# HVIB_v5.net
KiCad netlist of a schematic drawn in EAGLE
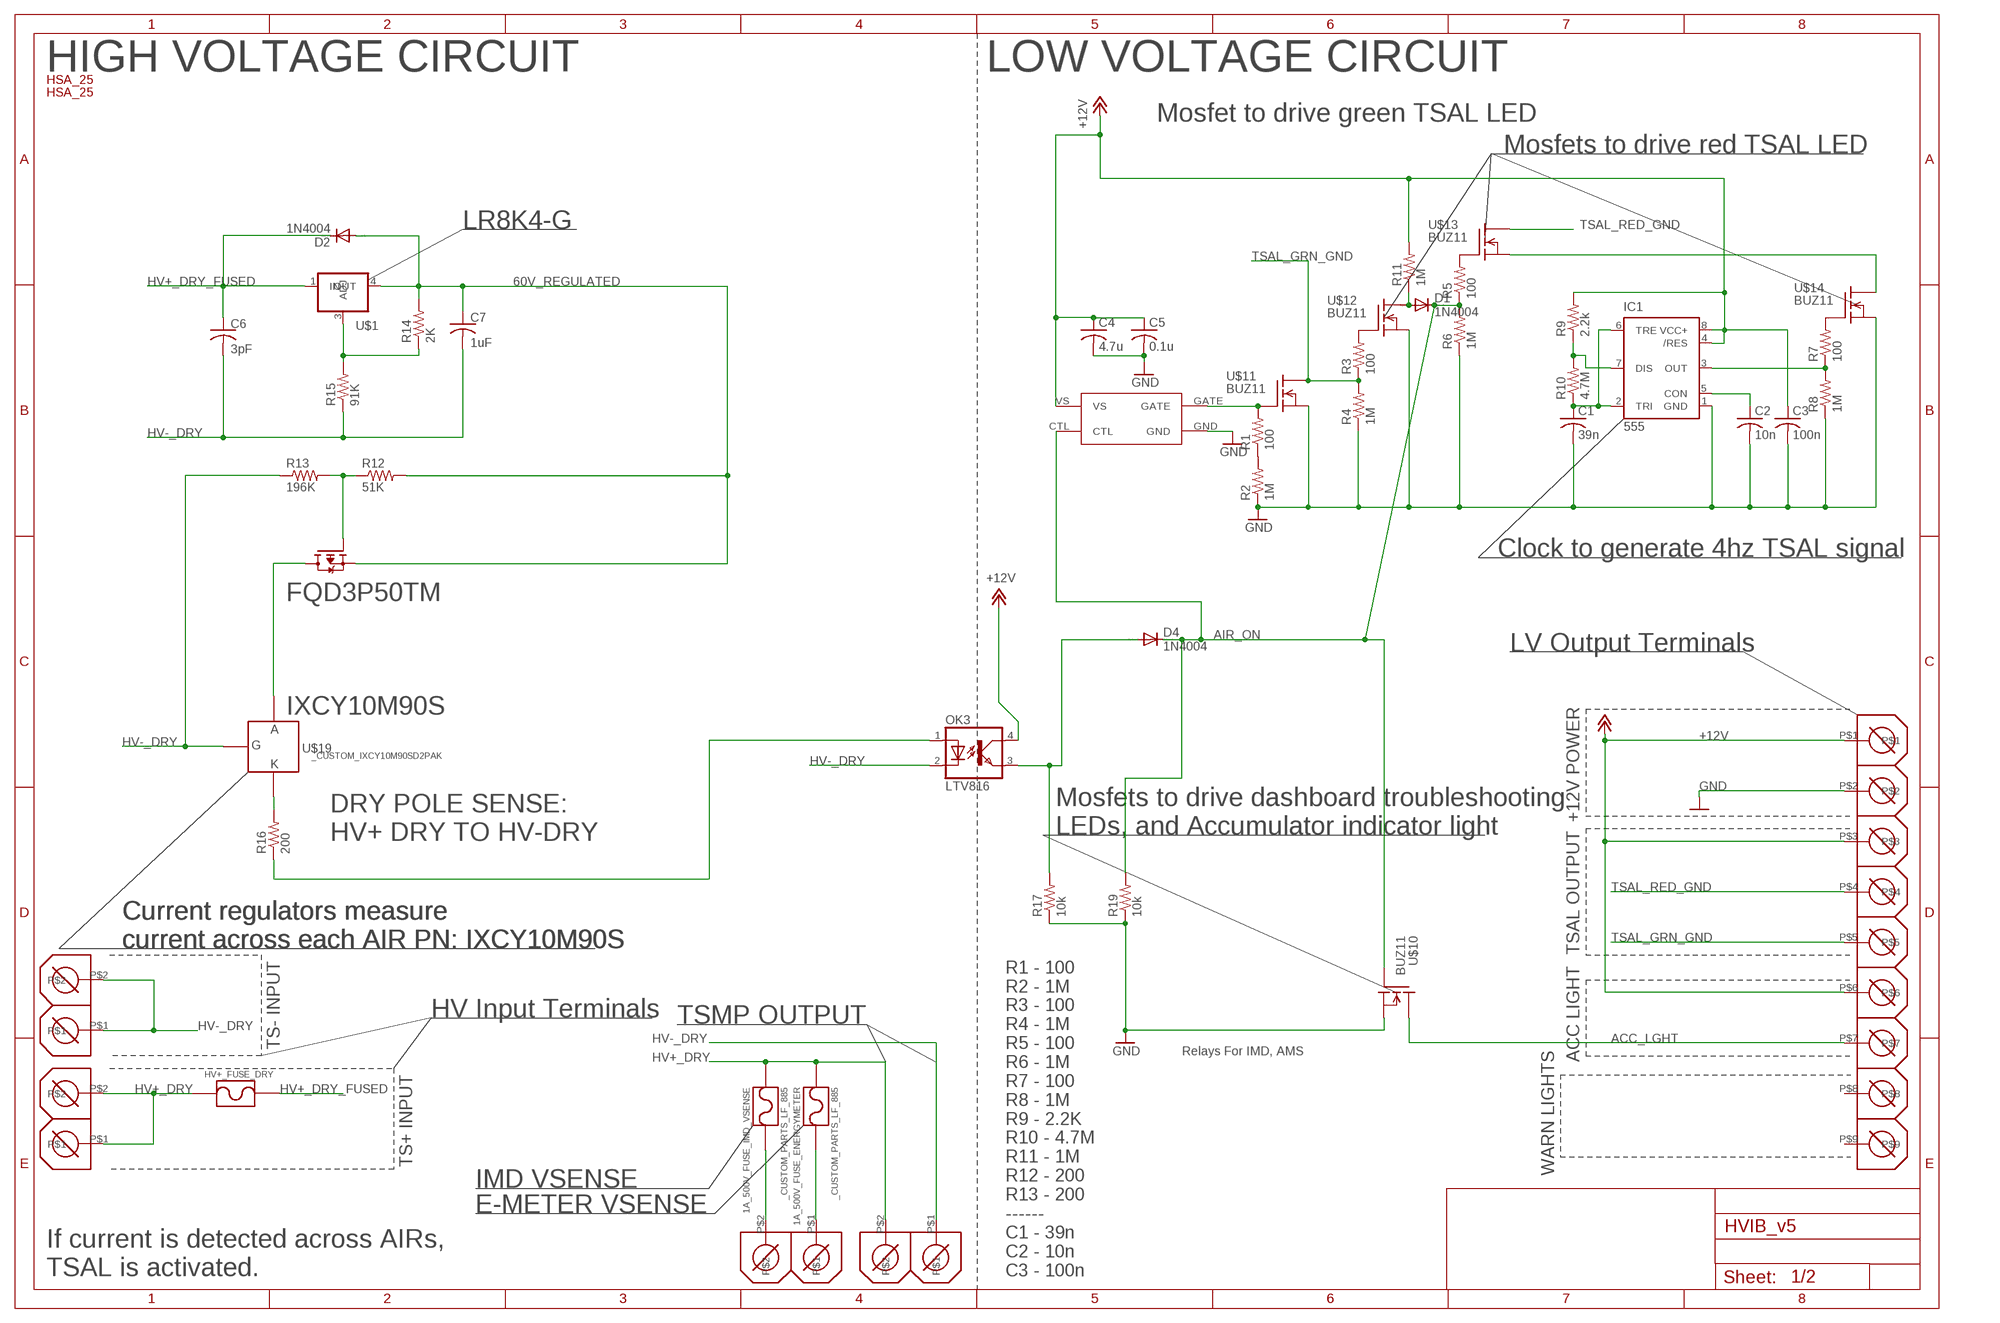
[diagram p0: schematic, sheet 1]
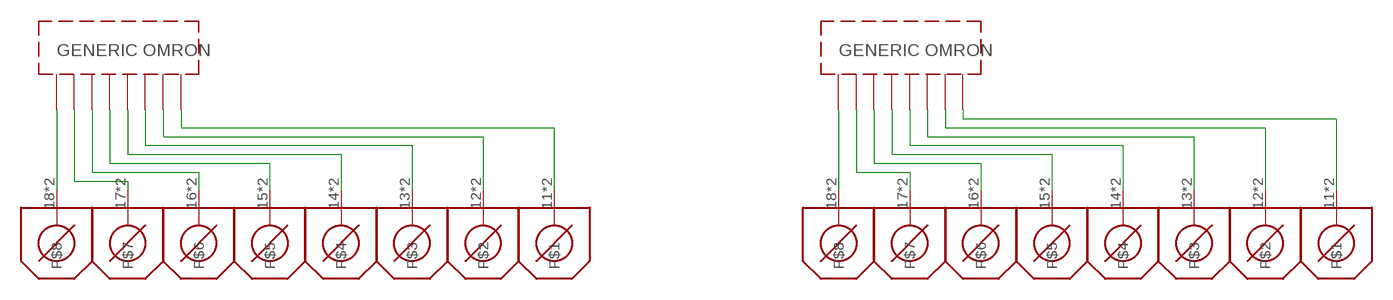
[diagram p1: schematic, sheet 2]

(export (version "E")
  (design (tool "Eeschema 10.0.6"))
  (components
    (comp (ref "1A_500V_FUSE_ENERGYMETER")
      (value "_CUSTOM_PARTS_LF_885")
      (footprint "eagle-import:_CUSTOM_PARTS_LF_885")
      (libsource (lib "eagle-import") (part "_CUSTOM_PARTS_LF_885"))
    )
    (comp (ref "1A_500V_FUSE_IMD_VSENSE")
      (value "_CUSTOM_PARTS_LF_885")
      (footprint "eagle-import:_CUSTOM_PARTS_LF_885")
      (libsource (lib "eagle-import") (part "_CUSTOM_PARTS_LF_885"))
    )
    (comp (ref "C1")
      (value "39n")
      (footprint "eagle-import:C0805")
      (libsource (lib "eagle-import") (part "resistor_348_C-USC0805"))
    )
    (comp (ref "C2")
      (value "10n")
      (footprint "eagle-import:C0805")
      (libsource (lib "eagle-import") (part "resistor_348_C-USC0805"))
    )
    (comp (ref "C3")
      (value "100n")
      (footprint "eagle-import:C0805")
      (libsource (lib "eagle-import") (part "resistor_348_C-USC0805"))
    )
    (comp (ref "C4")
      (value "4.7u")
      (footprint "eagle-import:C0805")
      (libsource (lib "eagle-import") (part "resistor_348_C-USC0805"))
    )
    (comp (ref "C5")
      (value "0.1u")
      (footprint "eagle-import:C0805")
      (libsource (lib "eagle-import") (part "resistor_348_C-USC0805"))
    )
    (comp (ref "C6")
      (value "3pF")
      (footprint "eagle-import:1111_2828METRIC")
      (libsource (lib "eagle-import") (part "CAP1111"))
    )
    (comp (ref "C7")
      (value "1uF")
      (footprint "eagle-import:C2220K")
      (libsource (lib "eagle-import") (part "C-USC2220K"))
    )
    (comp (ref "D1")
      (value "1N4004")
      (footprint "eagle-import:DO41-10")
      (libsource (lib "eagle-import") (part "1N4004"))
    )
    (comp (ref "D2")
      (value "1N4004")
      (footprint "eagle-import:DO41-10")
      (libsource (lib "eagle-import") (part "1N4004"))
    )
    (comp (ref "D4")
      (value "1N4004")
      (footprint "eagle-import:DO41-10")
      (libsource (lib "eagle-import") (part "1N4004"))
    )
    (comp (ref "FQD3P50TM")
      (value "FDD4141TO252")
      (footprint "eagle-import:TO252")
      (libsource (lib "eagle-import") (part "FDD4141TO252"))
    )
    (comp (ref "HV+_FUSE_DRY")
      (value "_CUSTOM_PARTS_LF_885")
      (footprint "eagle-import:_CUSTOM_PARTS_LF_885")
      (libsource (lib "eagle-import") (part "_CUSTOM_PARTS_LF_885"))
    )
    (comp (ref "IC1")
      (value "555")
      (footprint "eagle-import:DIP08")
      (libsource (lib "eagle-import") (part "555P"))
    )
    (comp (ref "OK3")
      (value "LTV816")
      (footprint "eagle-import:DIL04")
      (libsource (lib "eagle-import") (part "LTV816"))
    )
    (comp (ref "R1")
      (value "100")
      (footprint "eagle-import:R0805")
      (libsource (lib "eagle-import") (part "resistor_348_R-US_R0805"))
    )
    (comp (ref "R2")
      (value "1M")
      (footprint "eagle-import:R0805")
      (libsource (lib "eagle-import") (part "resistor_348_R-US_R0805"))
    )
    (comp (ref "R3")
      (value "100")
      (footprint "eagle-import:R0805")
      (libsource (lib "eagle-import") (part "resistor_348_R-US_R0805"))
    )
    (comp (ref "R4")
      (value "1M")
      (footprint "eagle-import:R0805")
      (libsource (lib "eagle-import") (part "resistor_348_R-US_R0805"))
    )
    (comp (ref "R5")
      (value "100")
      (footprint "eagle-import:R0805")
      (libsource (lib "eagle-import") (part "resistor_348_R-US_R0805"))
    )
    (comp (ref "R6")
      (value "1M")
      (footprint "eagle-import:R0805")
      (libsource (lib "eagle-import") (part "resistor_348_R-US_R0805"))
    )
    (comp (ref "R7")
      (value "100")
      (footprint "eagle-import:R0805")
      (libsource (lib "eagle-import") (part "resistor_348_R-US_R0805"))
    )
    (comp (ref "R8")
      (value "1M")
      (footprint "eagle-import:R0805")
      (libsource (lib "eagle-import") (part "resistor_348_R-US_R0805"))
    )
    (comp (ref "R9")
      (value "2.2k")
      (footprint "eagle-import:R0805")
      (libsource (lib "eagle-import") (part "resistor_348_R-US_R0805"))
    )
    (comp (ref "R10")
      (value "4.7M")
      (footprint "eagle-import:R0805")
      (libsource (lib "eagle-import") (part "resistor_348_R-US_R0805"))
    )
    (comp (ref "R11")
      (value "1M")
      (footprint "eagle-import:R0805")
      (libsource (lib "eagle-import") (part "resistor_348_R-US_R0805"))
    )
    (comp (ref "R12")
      (value "51K")
      (footprint "eagle-import:R2010")
      (libsource (lib "eagle-import") (part "R-US_R2010"))
    )
    (comp (ref "R13")
      (value "196K")
      (footprint "eagle-import:R2010")
      (libsource (lib "eagle-import") (part "R-US_R2010"))
    )
    (comp (ref "R14")
      (value "2K")
      (footprint "eagle-import:R2010")
      (libsource (lib "eagle-import") (part "R-US_R2010"))
    )
    (comp (ref "R15")
      (value "91K")
      (footprint "eagle-import:R2010")
      (libsource (lib "eagle-import") (part "R-US_R2010"))
    )
    (comp (ref "R16")
      (value "200")
      (footprint "eagle-import:R2010")
      (libsource (lib "eagle-import") (part "R-US_R2010"))
    )
    (comp (ref "R17")
      (value "10k")
      (footprint "eagle-import:R0805")
      (libsource (lib "eagle-import") (part "resistor_348_R-US_R0805"))
    )
    (comp (ref "R19")
      (value "10k")
      (footprint "eagle-import:R0805")
      (libsource (lib "eagle-import") (part "resistor_348_R-US_R0805"))
    )
    (comp (ref "U$1") (value "K4") (footprint "eagle-import:K4") (libsource (lib "eagle-import") (part "K4")))
    (comp (ref "U$2")
      (value "HSA25")
      (footprint "eagle-import:HSA_25_FOOT")
      (libsource (lib "eagle-import") (part "HSA25"))
    )
    (comp (ref "U$3")
      (value "HSA25")
      (footprint "eagle-import:HSA_25_FOOT")
      (libsource (lib "eagle-import") (part "HSA25"))
    )
    (comp (ref "U$4")
      (value "DCDC_PARTS_282838-2_TE")
      (footprint "eagle-import:DCDC_PARTS_282838-2_FOOT")
      (libsource (lib "eagle-import") (part "DCDC_PARTS_282838-2_TE"))
    )
    (comp (ref "U$6")
      (value "DCDC_PARTS_282838-2_TE")
      (footprint "eagle-import:DCDC_PARTS_282838-2_FOOT")
      (libsource (lib "eagle-import") (part "DCDC_PARTS_282838-2_TE"))
    )
    (comp (ref "U$7")
      (value "PHOENIX_1725724")
      (footprint "eagle-import:1725724_FOOT")
      (libsource (lib "eagle-import") (part "PHOENIX_1725724"))
    )
    (comp (ref "U$10")
      (value "BUZ11")
      (footprint "eagle-import:TO220")
      (libsource (lib "eagle-import") (part "BUZ11"))
    )
    (comp (ref "U$11")
      (value "BUZ11")
      (footprint "eagle-import:TO220")
      (libsource (lib "eagle-import") (part "BUZ11"))
    )
    (comp (ref "U$12")
      (value "BUZ11")
      (footprint "eagle-import:TO220")
      (libsource (lib "eagle-import") (part "BUZ11"))
    )
    (comp (ref "U$13")
      (value "BUZ11")
      (footprint "eagle-import:TO220")
      (libsource (lib "eagle-import") (part "BUZ11"))
    )
    (comp (ref "U$14")
      (value "BUZ11")
      (footprint "eagle-import:TO220")
      (libsource (lib "eagle-import") (part "BUZ11"))
    )
    (comp (ref "U$15")
      (value "MIC4417")
      (footprint "eagle-import:PDM_2019_REVB_MIC4416YM4-TR")
      (libsource (lib "eagle-import") (part "MIC4417"))
    )
    (comp (ref "U$16")
      (value "DCDC_PARTS_282838-2_TE")
      (footprint "eagle-import:DCDC_PARTS_282838-2_FOOT")
      (libsource (lib "eagle-import") (part "DCDC_PARTS_282838-2_TE"))
    )
    (comp (ref "U$17")
      (value "DCDC_PARTS_282838-2_TE")
      (footprint "eagle-import:DCDC_PARTS_282838-2_FOOT")
      (libsource (lib "eagle-import") (part "DCDC_PARTS_282838-2_TE"))
    )
    (comp (ref "U$19")
      (value "_CUSTOM_IXCY10M90SD2PAK")
      (footprint "eagle-import:TO228P991X238-3")
      (libsource (lib "eagle-import") (part "_CUSTOM_IXCY10M90SD2PAK"))
    )
    (comp (ref "U$5")
      (value "G2R_RLY")
      (footprint "eagle-import:OMRON_RLY_FOOT")
      (libsource (lib "eagle-import") (part "G2R_RLY"))
    )
    (comp (ref "U$8")
      (value "G2R_RLY")
      (footprint "eagle-import:OMRON_RLY_FOOT")
      (libsource (lib "eagle-import") (part "G2R_RLY"))
    )
    (comp (ref "U$9")
      (value "PHOENIX_1771017")
      (footprint "eagle-import:8PIN_HEAD")
      (libsource (lib "eagle-import") (part "PHOENIX_1771017"))
    )
    (comp (ref "U$18")
      (value "PHOENIX_1771017")
      (footprint "eagle-import:8PIN_HEAD")
      (libsource (lib "eagle-import") (part "PHOENIX_1771017"))
    )
  )
  (nets
    (net (code "1") (name "+12V") (class "Default")
      (node (ref "C3") (pin "1") (pinfunction "1_1") (pintype "passive"))
      (node (ref "C4") (pin "1") (pinfunction "1_1") (pintype "passive"))
      (node (ref "C5") (pin "1") (pinfunction "1_1") (pintype "passive"))
      (node (ref "IC1") (pin "4") (pinfunction "/RES_4") (pintype "input"))
      (node (ref "IC1") (pin "8") (pinfunction "VCC+_8") (pintype "power_in"))
      (node (ref "OK3") (pin "4") (pinfunction "COL_4") (pintype "passive"))
      (node (ref "R11") (pin "2") (pinfunction "2_2") (pintype "passive"))
      (node (ref "R9") (pin "2") (pinfunction "2_2") (pintype "passive"))
      (node (ref "U$15") (pin "VS") (pinfunction "VS_VS") (pintype "bidirectional"))
      (node (ref "U$7") (pin "P$1") (pinfunction "P$1_P$1") (pintype "bidirectional"))
      (node (ref "U$7") (pin "P$3") (pinfunction "P$3_P$3") (pintype "bidirectional"))
      (node (ref "U$7") (pin "P$6") (pinfunction "P$6_P$6") (pintype "bidirectional"))
    )
    (net (code "2") (name "60V_REGULATED") (class "Default")
      (node (ref "C7") (pin "1") (pinfunction "1_1") (pintype "passive"))
      (node (ref "D2") (pin "A") (pinfunction "A_A") (pintype "passive"))
      (node (ref "FQD3P50TM") (pin "2") (pinfunction "S_2") (pintype "passive"))
      (node (ref "R12") (pin "2") (pinfunction "2_2") (pintype "passive"))
      (node (ref "R14") (pin "2") (pinfunction "2_2") (pintype "passive"))
      (node (ref "U$1") (pin "4") (pinfunction "OUT_4") (pintype "output"))
    )
    (net (code "3") (name "ACC_LGHT") (class "Default")
      (node (ref "U$10") (pin "2") (pinfunction "D_2") (pintype "passive"))
      (node (ref "U$7") (pin "P$7") (pinfunction "P$7_P$7") (pintype "bidirectional"))
    )
    (net (code "4") (name "AIR_ON") (class "Default")
      (node (ref "D1") (pin "C") (pinfunction "C_C") (pintype "passive"))
      (node (ref "D4") (pin "C") (pinfunction "C_C") (pintype "passive"))
      (node (ref "R19") (pin "2") (pinfunction "2_2") (pintype "passive"))
      (node (ref "R5") (pin "1") (pinfunction "1_1") (pintype "passive"))
      (node (ref "R6") (pin "2") (pinfunction "2_2") (pintype "passive"))
      (node (ref "U$10") (pin "1") (pinfunction "G_1") (pintype "passive"))
      (node (ref "U$15") (pin "CTL") (pinfunction "CTL_CTL") (pintype "bidirectional"))
    )
    (net (code "5") (name "GND") (class "Default")
      (node (ref "C1") (pin "2") (pinfunction "2_2") (pintype "passive"))
      (node (ref "C2") (pin "2") (pinfunction "2_2") (pintype "passive"))
      (node (ref "C3") (pin "2") (pinfunction "2_2") (pintype "passive"))
      (node (ref "C4") (pin "2") (pinfunction "2_2") (pintype "passive"))
      (node (ref "C5") (pin "2") (pinfunction "2_2") (pintype "passive"))
      (node (ref "IC1") (pin "1") (pinfunction "GND_1") (pintype "power_in"))
      (node (ref "R17") (pin "1") (pinfunction "1_1") (pintype "passive"))
      (node (ref "R19") (pin "1") (pinfunction "1_1") (pintype "passive"))
      (node (ref "R2") (pin "1") (pinfunction "1_1") (pintype "passive"))
      (node (ref "R4") (pin "1") (pinfunction "1_1") (pintype "passive"))
      (node (ref "R6") (pin "1") (pinfunction "1_1") (pintype "passive"))
      (node (ref "R8") (pin "1") (pinfunction "1_1") (pintype "passive"))
      (node (ref "U$10") (pin "3") (pinfunction "S_3") (pintype "passive"))
      (node (ref "U$11") (pin "3") (pinfunction "S_3") (pintype "passive"))
      (node (ref "U$12") (pin "3") (pinfunction "S_3") (pintype "passive"))
      (node (ref "U$14") (pin "3") (pinfunction "S_3") (pintype "passive"))
      (node (ref "U$15") (pin "GND") (pinfunction "GND_GND") (pintype "bidirectional"))
      (node (ref "U$7") (pin "P$2") (pinfunction "P$2_P$2") (pintype "bidirectional"))
    )
    (net (code "6") (name "HV+_DRY") (class "Default")
      (node (ref "1A_500V_FUSE_ENERGYMETER") (pin "P$1") (pinfunction "P$1_P$1") (pintype "bidirectional"))
      (node (ref "1A_500V_FUSE_IMD_VSENSE") (pin "P$1") (pinfunction "P$1_P$1") (pintype "bidirectional"))
      (node (ref "HV+_FUSE_DRY") (pin "P$2") (pinfunction "P$2_P$2") (pintype "bidirectional"))
      (node (ref "U$16") (pin "P$2") (pinfunction "P$2_P$2") (pintype "bidirectional"))
      (node (ref "U$6") (pin "P$1") (pinfunction "P$1_P$1") (pintype "bidirectional"))
      (node (ref "U$6") (pin "P$2") (pinfunction "P$2_P$2") (pintype "bidirectional"))
    )
    (net (code "7") (name "HV+_DRY_FUSED") (class "Default")
      (node (ref "C6") (pin "P$1") (pinfunction "1_P$1") (pintype "passive"))
      (node (ref "D2") (pin "C") (pinfunction "C_C") (pintype "passive"))
      (node (ref "HV+_FUSE_DRY") (pin "P$1") (pinfunction "P$1_P$1") (pintype "bidirectional"))
      (node (ref "U$1") (pin "1") (pinfunction "IN_1") (pintype "input"))
    )
    (net (code "8") (name "HV-_DRY") (class "Default")
      (node (ref "C6") (pin "P$2") (pinfunction "2_P$2") (pintype "passive"))
      (node (ref "C7") (pin "2") (pinfunction "2_2") (pintype "passive"))
      (node (ref "OK3") (pin "2") (pinfunction "C_2") (pintype "passive"))
      (node (ref "R13") (pin "1") (pinfunction "1_1") (pintype "passive"))
      (node (ref "R15") (pin "1") (pinfunction "1_1") (pintype "passive"))
      (node (ref "U$16") (pin "P$1") (pinfunction "P$1_P$1") (pintype "bidirectional"))
      (node (ref "U$19") (pin "1") (pinfunction "G_1") (pintype "bidirectional"))
      (node (ref "U$4") (pin "P$1") (pinfunction "P$1_P$1") (pintype "bidirectional"))
      (node (ref "U$4") (pin "P$2") (pinfunction "P$2_P$2") (pintype "bidirectional"))
    )
    (net (code "9") (name "Net-(1A_500V_FUSE_ENERGYMETER-PadP$2)") (class "Default")
      (node (ref "1A_500V_FUSE_ENERGYMETER") (pin "P$2") (pinfunction "P$2_P$2") (pintype "bidirectional"))
      (node (ref "U$17") (pin "P$1") (pinfunction "P$1_P$1") (pintype "bidirectional"))
    )
    (net (code "10") (name "Net-(1A_500V_FUSE_IMD_VSENSE-PadP$2)") (class "Default")
      (node (ref "1A_500V_FUSE_IMD_VSENSE") (pin "P$2") (pinfunction "P$2_P$2") (pintype "bidirectional"))
      (node (ref "U$17") (pin "P$2") (pinfunction "P$2_P$2") (pintype "bidirectional"))
    )
    (net (code "11") (name "Net-(FQD3P50TM-D)") (class "Default")
      (node (ref "FQD3P50TM") (pin "3") (pinfunction "D_3") (pintype "passive"))
      (node (ref "U$19") (pin "3") (pinfunction "A_3") (pintype "bidirectional"))
    )
    (net (code "12") (name "Net-(FQD3P50TM-G)") (class "Default")
      (node (ref "FQD3P50TM") (pin "1") (pinfunction "G_1") (pintype "passive"))
      (node (ref "R12") (pin "1") (pinfunction "1_1") (pintype "passive"))
      (node (ref "R13") (pin "2") (pinfunction "2_2") (pintype "passive"))
    )
    (net (code "13") (name "Net-(IC1-CON)") (class "Default")
      (node (ref "C2") (pin "1") (pinfunction "1_1") (pintype "passive"))
      (node (ref "IC1") (pin "5") (pinfunction "CON_5") (pintype "input"))
    )
    (net (code "14") (name "Net-(IC1-DIS)") (class "Default")
      (node (ref "IC1") (pin "7") (pinfunction "DIS_7") (pintype "input"))
      (node (ref "R10") (pin "2") (pinfunction "2_2") (pintype "passive"))
      (node (ref "R9") (pin "1") (pinfunction "1_1") (pintype "passive"))
    )
    (net (code "15") (name "Net-(IC1-OUT)") (class "Default")
      (node (ref "IC1") (pin "3") (pinfunction "OUT_3") (pintype "output"))
      (node (ref "R7") (pin "1") (pinfunction "1_1") (pintype "passive"))
      (node (ref "R8") (pin "2") (pinfunction "2_2") (pintype "passive"))
    )
    (net (code "16") (name "Net-(IC1-TRE)") (class "Default")
      (node (ref "C1") (pin "1") (pinfunction "1_1") (pintype "passive"))
      (node (ref "IC1") (pin "2") (pinfunction "TRI_2") (pintype "input"))
      (node (ref "IC1") (pin "6") (pinfunction "TRE_6") (pintype "input"))
      (node (ref "R10") (pin "1") (pinfunction "1_1") (pintype "passive"))
    )
    (net (code "17") (name "Net-(OK3-A)") (class "Default")
      (node (ref "OK3") (pin "1") (pinfunction "A_1") (pintype "passive"))
      (node (ref "R16") (pin "1") (pinfunction "1_1") (pintype "passive"))
    )
    (net (code "18") (name "Net-(OK3-EMIT)") (class "Default")
      (node (ref "D4") (pin "A") (pinfunction "A_A") (pintype "passive"))
      (node (ref "OK3") (pin "3") (pinfunction "EMIT_3") (pintype "passive"))
      (node (ref "R17") (pin "2") (pinfunction "2_2") (pintype "passive"))
    )
    (net (code "19") (name "Net-(R1-Pad1)") (class "Default")
      (node (ref "R1") (pin "1") (pinfunction "1_1") (pintype "passive"))
      (node (ref "R2") (pin "2") (pinfunction "2_2") (pintype "passive"))
    )
    (net (code "20") (name "Net-(U$1-ADJ)") (class "Default")
      (node (ref "R14") (pin "1") (pinfunction "1_1") (pintype "passive"))
      (node (ref "R15") (pin "2") (pinfunction "2_2") (pintype "passive"))
      (node (ref "U$1") (pin "3") (pinfunction "ADJ_3") (pintype "input"))
    )
    (net (code "21") (name "Net-(U$5-Pad1)") (class "Default")
      (node (ref "U$5") (pin "1") (pinfunction "1_1") (pintype "bidirectional"))
      (node (ref "U$9") (pin "18") (pinfunction "P$8_18") (pintype "bidirectional"))
      (node (ref "U$9") (pin "28") (pinfunction "P$8_28") (pintype "bidirectional"))
    )
    (net (code "22") (name "Net-(U$5-Pad2)") (class "Default")
      (node (ref "U$5") (pin "2") (pinfunction "2_2") (pintype "bidirectional"))
      (node (ref "U$9") (pin "17") (pinfunction "P$7_17") (pintype "bidirectional"))
      (node (ref "U$9") (pin "27") (pinfunction "P$7_27") (pintype "bidirectional"))
    )
    (net (code "23") (name "Net-(U$5-Pad3)") (class "Default")
      (node (ref "U$5") (pin "3") (pinfunction "3_3") (pintype "bidirectional"))
      (node (ref "U$9") (pin "16") (pinfunction "P$6_16") (pintype "bidirectional"))
      (node (ref "U$9") (pin "26") (pinfunction "P$6_26") (pintype "bidirectional"))
    )
    (net (code "24") (name "Net-(U$5-Pad4)") (class "Default")
      (node (ref "U$5") (pin "4") (pinfunction "4_4") (pintype "bidirectional"))
      (node (ref "U$9") (pin "15") (pinfunction "P$5_15") (pintype "bidirectional"))
      (node (ref "U$9") (pin "25") (pinfunction "P$5_25") (pintype "bidirectional"))
    )
    (net (code "25") (name "Net-(U$5-Pad5)") (class "Default")
      (node (ref "U$5") (pin "5") (pinfunction "5_5") (pintype "bidirectional"))
      (node (ref "U$9") (pin "14") (pinfunction "P$4_14") (pintype "bidirectional"))
      (node (ref "U$9") (pin "24") (pinfunction "P$4_24") (pintype "bidirectional"))
    )
    (net (code "26") (name "Net-(U$5-Pad6)") (class "Default")
      (node (ref "U$5") (pin "6") (pinfunction "6_6") (pintype "bidirectional"))
      (node (ref "U$9") (pin "13") (pinfunction "P$3_13") (pintype "bidirectional"))
      (node (ref "U$9") (pin "23") (pinfunction "P$3_23") (pintype "bidirectional"))
    )
    (net (code "27") (name "Net-(U$5-Pad7)") (class "Default")
      (node (ref "U$5") (pin "7") (pinfunction "7_7") (pintype "bidirectional"))
      (node (ref "U$9") (pin "12") (pinfunction "P$2_12") (pintype "bidirectional"))
      (node (ref "U$9") (pin "22") (pinfunction "P$2_22") (pintype "bidirectional"))
    )
    (net (code "28") (name "Net-(U$5-Pad8)") (class "Default")
      (node (ref "U$5") (pin "8") (pinfunction "8_8") (pintype "bidirectional"))
      (node (ref "U$9") (pin "11") (pinfunction "P$1_11") (pintype "bidirectional"))
      (node (ref "U$9") (pin "21") (pinfunction "P$1_21") (pintype "bidirectional"))
    )
    (net (code "29") (name "Net-(U$11-G)") (class "Default")
      (node (ref "R1") (pin "2") (pinfunction "2_2") (pintype "passive"))
      (node (ref "U$11") (pin "1") (pinfunction "G_1") (pintype "passive"))
      (node (ref "U$15") (pin "GATE") (pinfunction "GATE_GATE") (pintype "bidirectional"))
    )
    (net (code "30") (name "Net-(U$12-D)") (class "Default")
      (node (ref "D1") (pin "A") (pinfunction "A_A") (pintype "passive"))
      (node (ref "R11") (pin "1") (pinfunction "1_1") (pintype "passive"))
      (node (ref "U$12") (pin "2") (pinfunction "D_2") (pintype "passive"))
    )
    (net (code "31") (name "Net-(U$12-G)") (class "Default")
      (node (ref "R3") (pin "2") (pinfunction "2_2") (pintype "passive"))
      (node (ref "U$12") (pin "1") (pinfunction "G_1") (pintype "passive"))
    )
    (net (code "32") (name "Net-(U$13-G)") (class "Default")
      (node (ref "R5") (pin "2") (pinfunction "2_2") (pintype "passive"))
      (node (ref "U$13") (pin "1") (pinfunction "G_1") (pintype "passive"))
    )
    (net (code "33") (name "Net-(U$13-S)") (class "Default")
      (node (ref "U$13") (pin "3") (pinfunction "S_3") (pintype "passive"))
      (node (ref "U$14") (pin "2") (pinfunction "D_2") (pintype "passive"))
    )
    (net (code "34") (name "Net-(U$14-G)") (class "Default")
      (node (ref "R7") (pin "2") (pinfunction "2_2") (pintype "passive"))
      (node (ref "U$14") (pin "1") (pinfunction "G_1") (pintype "passive"))
    )
    (net (code "35") (name "Net-(U$18-P$1-Pad11)") (class "Default")
      (node (ref "U$18") (pin "11") (pinfunction "P$1_11") (pintype "bidirectional"))
      (node (ref "U$18") (pin "21") (pinfunction "P$1_21") (pintype "bidirectional"))
      (node (ref "U$8") (pin "8") (pinfunction "8_8") (pintype "bidirectional"))
    )
    (net (code "36") (name "Net-(U$18-P$2-Pad12)") (class "Default")
      (node (ref "U$18") (pin "12") (pinfunction "P$2_12") (pintype "bidirectional"))
      (node (ref "U$18") (pin "22") (pinfunction "P$2_22") (pintype "bidirectional"))
      (node (ref "U$8") (pin "7") (pinfunction "7_7") (pintype "bidirectional"))
    )
    (net (code "37") (name "Net-(U$18-P$3-Pad13)") (class "Default")
      (node (ref "U$18") (pin "13") (pinfunction "P$3_13") (pintype "bidirectional"))
      (node (ref "U$18") (pin "23") (pinfunction "P$3_23") (pintype "bidirectional"))
      (node (ref "U$8") (pin "6") (pinfunction "6_6") (pintype "bidirectional"))
    )
    (net (code "38") (name "Net-(U$18-P$4-Pad14)") (class "Default")
      (node (ref "U$18") (pin "14") (pinfunction "P$4_14") (pintype "bidirectional"))
      (node (ref "U$18") (pin "24") (pinfunction "P$4_24") (pintype "bidirectional"))
      (node (ref "U$8") (pin "5") (pinfunction "5_5") (pintype "bidirectional"))
    )
    (net (code "39") (name "Net-(U$18-P$5-Pad15)") (class "Default")
      (node (ref "U$18") (pin "15") (pinfunction "P$5_15") (pintype "bidirectional"))
      (node (ref "U$18") (pin "25") (pinfunction "P$5_25") (pintype "bidirectional"))
      (node (ref "U$8") (pin "4") (pinfunction "4_4") (pintype "bidirectional"))
    )
    (net (code "40") (name "Net-(U$18-P$6-Pad16)") (class "Default")
      (node (ref "U$18") (pin "16") (pinfunction "P$6_16") (pintype "bidirectional"))
      (node (ref "U$18") (pin "26") (pinfunction "P$6_26") (pintype "bidirectional"))
      (node (ref "U$8") (pin "3") (pinfunction "3_3") (pintype "bidirectional"))
    )
    (net (code "41") (name "Net-(U$18-P$7-Pad17)") (class "Default")
      (node (ref "U$18") (pin "17") (pinfunction "P$7_17") (pintype "bidirectional"))
      (node (ref "U$18") (pin "27") (pinfunction "P$7_27") (pintype "bidirectional"))
      (node (ref "U$8") (pin "2") (pinfunction "2_2") (pintype "bidirectional"))
    )
    (net (code "42") (name "Net-(U$18-P$8-Pad18)") (class "Default")
      (node (ref "U$18") (pin "18") (pinfunction "P$8_18") (pintype "bidirectional"))
      (node (ref "U$18") (pin "28") (pinfunction "P$8_28") (pintype "bidirectional"))
      (node (ref "U$8") (pin "1") (pinfunction "1_1") (pintype "bidirectional"))
    )
    (net (code "43") (name "Net-(U$19-K)") (class "Default")
      (node (ref "R16") (pin "2") (pinfunction "2_2") (pintype "passive"))
      (node (ref "U$19") (pin "2") (pinfunction "K_2") (pintype "bidirectional"))
    )
    (net (code "44") (name "TSAL_GRN_GND") (class "Default")
      (node (ref "R3") (pin "1") (pinfunction "1_1") (pintype "passive"))
      (node (ref "R4") (pin "2") (pinfunction "2_2") (pintype "passive"))
      (node (ref "U$11") (pin "2") (pinfunction "D_2") (pintype "passive"))
      (node (ref "U$7") (pin "P$5") (pinfunction "P$5_P$5") (pintype "bidirectional"))
    )
    (net (code "45") (name "TSAL_RED_GND") (class "Default")
      (node (ref "U$13") (pin "2") (pinfunction "D_2") (pintype "passive"))
      (node (ref "U$7") (pin "P$4") (pinfunction "P$4_P$4") (pintype "bidirectional"))
    )
    (net (code "46") (name "unconnected-(U$7-PadP$8)") (class "Default")
      (node (ref "U$7") (pin "P$8") (pinfunction "P$8_P$8") (pintype "bidirectional"))
    )
    (net (code "47") (name "unconnected-(U$7-PadP$9)") (class "Default")
      (node (ref "U$7") (pin "P$9") (pinfunction "P$9_P$9") (pintype "bidirectional"))
    )
  )
)
